# 5V_-5V_3_3V_PowerSupply.net
KiCad netlist of a schematic drawn in EAGLE
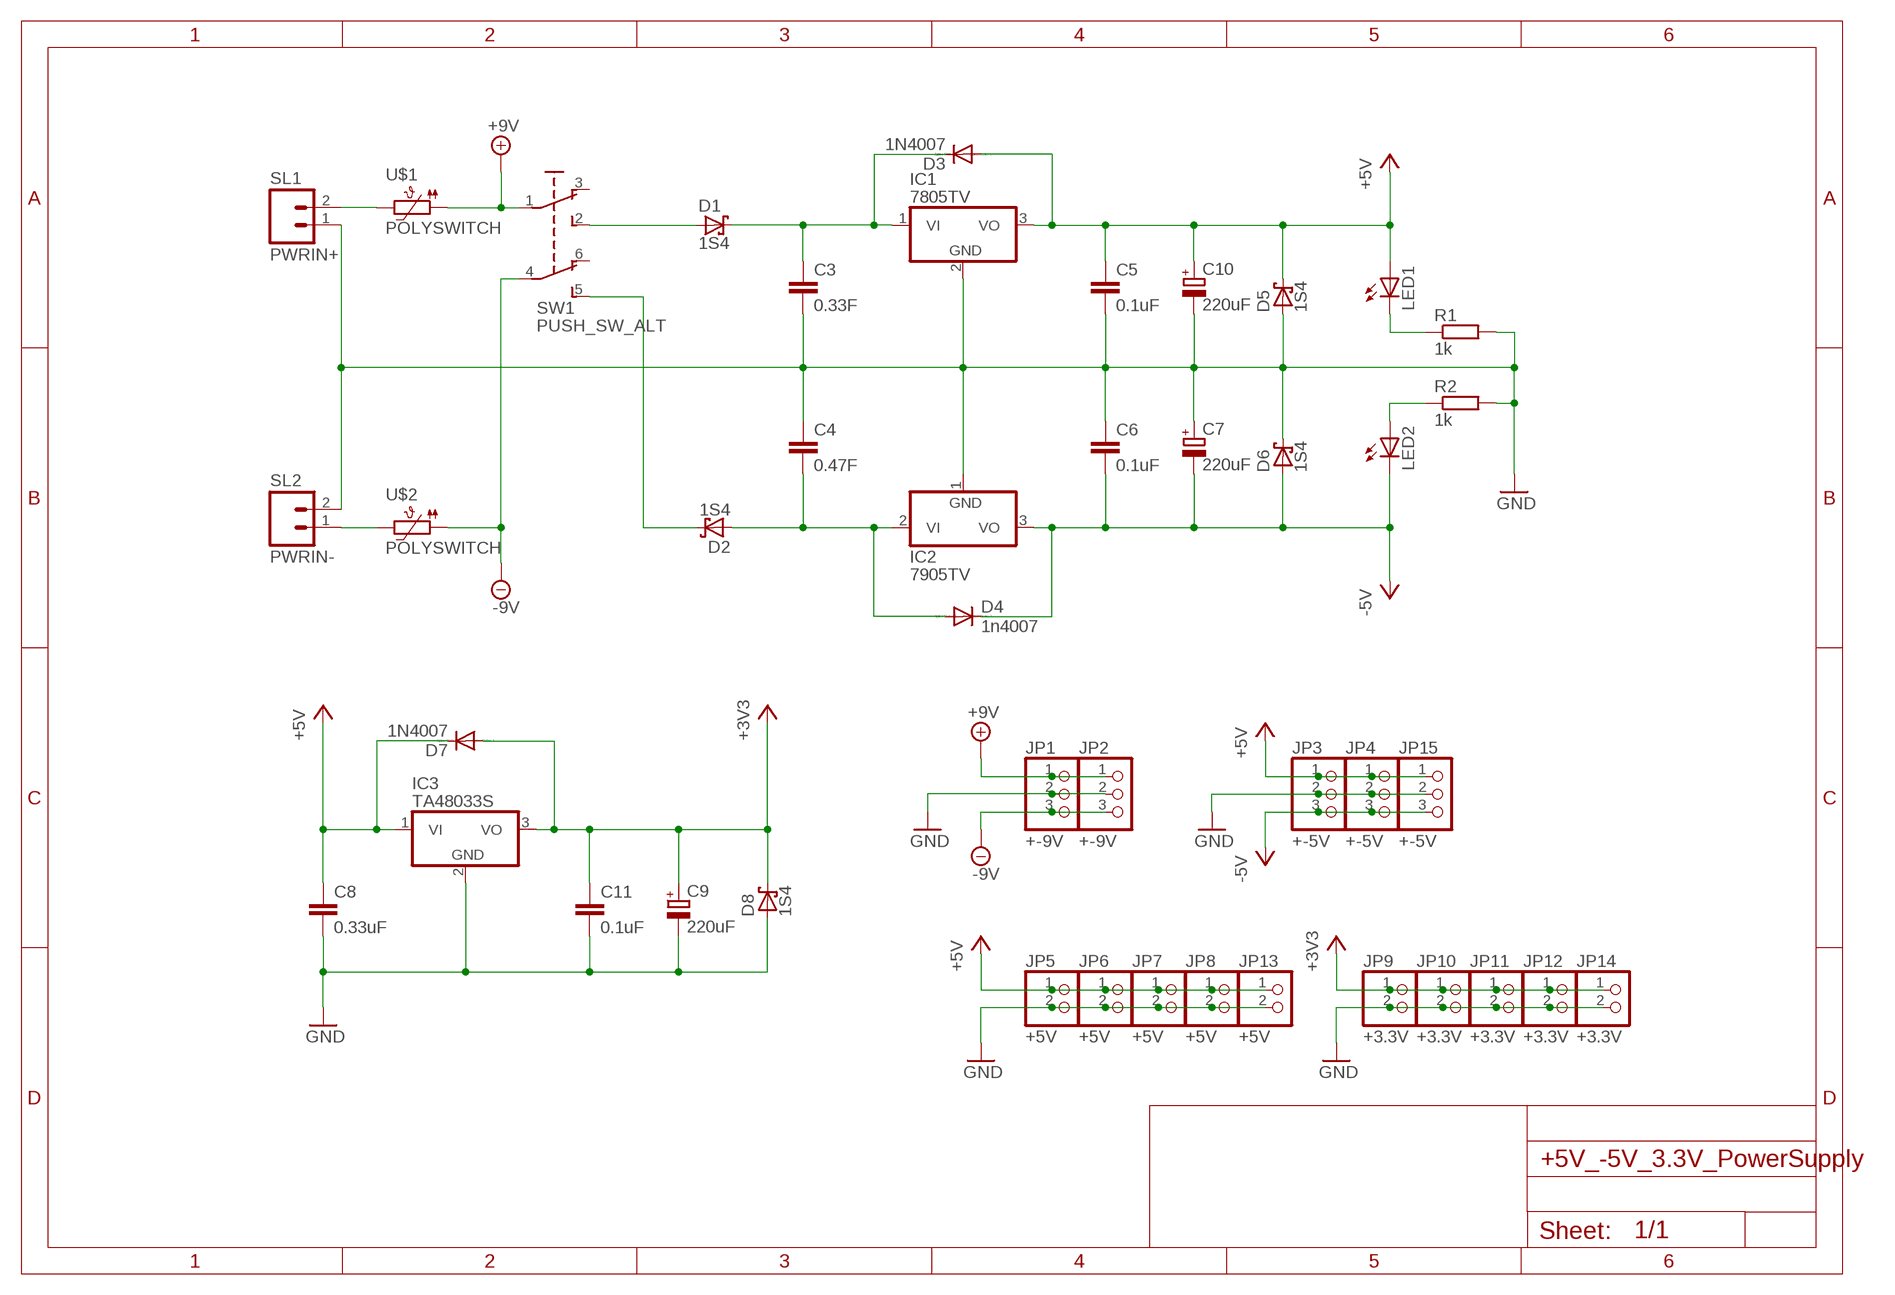
[diagram p0: schematic, sheet 1]

(export (version "E")
  (design (tool "Eeschema 10.0.6"))
  (components
    (comp (ref "C3")
      (value "0.33F")
      (footprint "eagle-import:C050-025X075")
      (libsource (lib "eagle-import") (part "C-EU050-025X075"))
    )
    (comp (ref "C4")
      (value "0.47F")
      (footprint "eagle-import:C050-025X075")
      (libsource (lib "eagle-import") (part "C-EU050-025X075"))
    )
    (comp (ref "C5")
      (value "0.1uF")
      (footprint "eagle-import:C050-024X044")
      (libsource (lib "eagle-import") (part "C-EU050-024X044"))
    )
    (comp (ref "C6")
      (value "0.1uF")
      (footprint "eagle-import:C050-024X044")
      (libsource (lib "eagle-import") (part "C-EU050-024X044"))
    )
    (comp (ref "C7")
      (value "220uF")
      (footprint "eagle-import:E2,5-6")
      (libsource (lib "eagle-import") (part "CPOL-EUE2.5-6"))
    )
    (comp (ref "C8")
      (value "0.33uF")
      (footprint "eagle-import:C050-025X075")
      (libsource (lib "eagle-import") (part "C-EU050-025X075"))
    )
    (comp (ref "C9")
      (value "220uF")
      (footprint "eagle-import:E2,5-6")
      (libsource (lib "eagle-import") (part "CPOL-EUE2.5-6"))
    )
    (comp (ref "C10")
      (value "220uF")
      (footprint "eagle-import:E2,5-6")
      (libsource (lib "eagle-import") (part "CPOL-EUE2.5-6"))
    )
    (comp (ref "C11")
      (value "0.1uF")
      (footprint "eagle-import:C050-025X075")
      (libsource (lib "eagle-import") (part "C-EU050-025X075"))
    )
    (comp (ref "D1")
      (value "1S4")
      (footprint "eagle-import:DO35-7")
      (libsource (lib "eagle-import") (part "SCHOTTKY-DIODEDO35-7"))
    )
    (comp (ref "D2")
      (value "1S4")
      (footprint "eagle-import:DO35-7")
      (libsource (lib "eagle-import") (part "SCHOTTKY-DIODEDO35-7"))
    )
    (comp (ref "D3")
      (value "1N4007")
      (footprint "eagle-import:D-7.5")
      (libsource (lib "eagle-import") (part "DIODE-D-7.5"))
    )
    (comp (ref "D4")
      (value "1n4007")
      (footprint "eagle-import:D-7.5")
      (libsource (lib "eagle-import") (part "DIODE-D-7.5"))
    )
    (comp (ref "D5")
      (value "1S4")
      (footprint "eagle-import:DO35-7")
      (libsource (lib "eagle-import") (part "SCHOTTKY-DIODEDO35-7"))
    )
    (comp (ref "D6")
      (value "1S4")
      (footprint "eagle-import:DO35-7")
      (libsource (lib "eagle-import") (part "SCHOTTKY-DIODEDO35-7"))
    )
    (comp (ref "D7")
      (value "1N4007")
      (footprint "eagle-import:D-7.5")
      (libsource (lib "eagle-import") (part "DIODE-D-7.5"))
    )
    (comp (ref "D8")
      (value "1S4")
      (footprint "eagle-import:DO35-7")
      (libsource (lib "eagle-import") (part "SCHOTTKY-DIODEDO35-7"))
    )
    (comp (ref "IC1")
      (value "7805TV")
      (footprint "eagle-import:TO220V")
      (libsource (lib "eagle-import") (part "78TV05"))
    )
    (comp (ref "IC2")
      (value "7905TV")
      (footprint "eagle-import:TO220V")
      (libsource (lib "eagle-import") (part "7905TV"))
    )
    (comp (ref "IC3")
      (value "TA48033S")
      (footprint "eagle-import:TO220V")
      (libsource (lib "eagle-import") (part "78TV05"))
    )
    (comp (ref "JP1")
      (value "+-9V")
      (footprint "eagle-import:1X03")
      (libsource (lib "eagle-import") (part "PINHD-1X3"))
    )
    (comp (ref "JP2")
      (value "+-9V")
      (footprint "eagle-import:1X03")
      (libsource (lib "eagle-import") (part "PINHD-1X3"))
    )
    (comp (ref "JP3")
      (value "+-5V")
      (footprint "eagle-import:1X03")
      (libsource (lib "eagle-import") (part "PINHD-1X3"))
    )
    (comp (ref "JP4")
      (value "+-5V")
      (footprint "eagle-import:1X03")
      (libsource (lib "eagle-import") (part "PINHD-1X3"))
    )
    (comp (ref "JP5")
      (value "+5V")
      (footprint "eagle-import:1X02")
      (libsource (lib "eagle-import") (part "PINHD-1X2"))
    )
    (comp (ref "JP6")
      (value "+5V")
      (footprint "eagle-import:1X02")
      (libsource (lib "eagle-import") (part "PINHD-1X2"))
    )
    (comp (ref "JP7")
      (value "+5V")
      (footprint "eagle-import:1X02")
      (libsource (lib "eagle-import") (part "PINHD-1X2"))
    )
    (comp (ref "JP8")
      (value "+5V")
      (footprint "eagle-import:1X02")
      (libsource (lib "eagle-import") (part "PINHD-1X2"))
    )
    (comp (ref "JP9")
      (value "+3.3V")
      (footprint "eagle-import:1X02")
      (libsource (lib "eagle-import") (part "PINHD-1X2"))
    )
    (comp (ref "JP10")
      (value "+3.3V")
      (footprint "eagle-import:1X02")
      (libsource (lib "eagle-import") (part "PINHD-1X2"))
    )
    (comp (ref "JP11")
      (value "+3.3V")
      (footprint "eagle-import:1X02")
      (libsource (lib "eagle-import") (part "PINHD-1X2"))
    )
    (comp (ref "JP12")
      (value "+3.3V")
      (footprint "eagle-import:1X02")
      (libsource (lib "eagle-import") (part "PINHD-1X2"))
    )
    (comp (ref "JP13")
      (value "+5V")
      (footprint "eagle-import:1X02")
      (libsource (lib "eagle-import") (part "PINHD-1X2"))
    )
    (comp (ref "JP14")
      (value "+3.3V")
      (footprint "eagle-import:1X02")
      (libsource (lib "eagle-import") (part "PINHD-1X2"))
    )
    (comp (ref "JP15")
      (value "+-5V")
      (footprint "eagle-import:1X03")
      (libsource (lib "eagle-import") (part "PINHD-1X3"))
    )
    (comp (ref "LED1")
      (value "LED3MM")
      (footprint "eagle-import:LED3MM")
      (libsource (lib "eagle-import") (part "LED3MM"))
    )
    (comp (ref "LED2")
      (value "LED3MM")
      (footprint "eagle-import:LED3MM")
      (libsource (lib "eagle-import") (part "LED3MM"))
    )
    (comp (ref "R1")
      (value "1k")
      (footprint "eagle-import:0207_7")
      (libsource (lib "eagle-import") (part "R-EU_0207/7"))
    )
    (comp (ref "R2")
      (value "1k")
      (footprint "eagle-import:0207_7")
      (libsource (lib "eagle-import") (part "R-EU_0207/7"))
    )
    (comp (ref "SL1")
      (value "PWRIN+")
      (footprint "eagle-import:02P")
      (libsource (lib "eagle-import") (part "M02"))
    )
    (comp (ref "SL2")
      (value "PWRIN-")
      (footprint "eagle-import:02P")
      (libsource (lib "eagle-import") (part "M02"))
    )
    (comp (ref "SW1")
      (value "PUSH_SW_ALT")
      (footprint "eagle-import:PUSH_SW_ALT")
      (libsource (lib "eagle-import") (part "PUSH_SW_ALT"))
    )
    (comp (ref "U$1")
      (value "POLYSWITCH")
      (footprint "eagle-import:POLYSWITCH")
      (libsource (lib "eagle-import") (part "POLYSWITCH"))
    )
    (comp (ref "U$2")
      (value "POLYSWITCH")
      (footprint "eagle-import:POLYSWITCH")
      (libsource (lib "eagle-import") (part "POLYSWITCH"))
    )
  )
  (nets
    (net (code "1") (name "+3V3") (class "Default")
      (node (ref "C11") (pin "1") (pinfunction "1_1") (pintype "passive"))
      (node (ref "C9") (pin "+") (pinfunction "+_+") (pintype "passive"))
      (node (ref "D7") (pin "A") (pinfunction "A_A") (pintype "passive"))
      (node (ref "D8") (pin "C") (pinfunction "C_C") (pintype "passive"))
      (node (ref "IC3") (pin "3") (pinfunction "VO_3") (pintype "passive"))
      (node (ref "JP10") (pin "1") (pinfunction "1_1") (pintype "passive"))
      (node (ref "JP11") (pin "1") (pinfunction "1_1") (pintype "passive"))
      (node (ref "JP12") (pin "1") (pinfunction "1_1") (pintype "passive"))
      (node (ref "JP14") (pin "1") (pinfunction "1_1") (pintype "passive"))
      (node (ref "JP9") (pin "1") (pinfunction "1_1") (pintype "passive"))
    )
    (net (code "2") (name "+5V") (class "Default")
      (node (ref "C10") (pin "+") (pinfunction "+_+") (pintype "passive"))
      (node (ref "C5") (pin "1") (pinfunction "1_1") (pintype "passive"))
      (node (ref "C8") (pin "1") (pinfunction "1_1") (pintype "passive"))
      (node (ref "D3") (pin "A") (pinfunction "A_A") (pintype "passive"))
      (node (ref "D5") (pin "C") (pinfunction "C_C") (pintype "passive"))
      (node (ref "D7") (pin "C") (pinfunction "C_C") (pintype "passive"))
      (node (ref "IC1") (pin "3") (pinfunction "VO_3") (pintype "passive"))
      (node (ref "IC3") (pin "1") (pinfunction "VI_1") (pintype "input"))
      (node (ref "JP13") (pin "1") (pinfunction "1_1") (pintype "passive"))
      (node (ref "JP15") (pin "1") (pinfunction "1_1") (pintype "passive"))
      (node (ref "JP3") (pin "1") (pinfunction "1_1") (pintype "passive"))
      (node (ref "JP4") (pin "1") (pinfunction "1_1") (pintype "passive"))
      (node (ref "JP5") (pin "1") (pinfunction "1_1") (pintype "passive"))
      (node (ref "JP6") (pin "1") (pinfunction "1_1") (pintype "passive"))
      (node (ref "JP7") (pin "1") (pinfunction "1_1") (pintype "passive"))
      (node (ref "JP8") (pin "1") (pinfunction "1_1") (pintype "passive"))
      (node (ref "LED1") (pin "A") (pinfunction "A_A") (pintype "passive"))
    )
    (net (code "3") (name "+9V") (class "Default")
      (node (ref "JP1") (pin "1") (pinfunction "1_1") (pintype "passive"))
      (node (ref "JP2") (pin "1") (pinfunction "1_1") (pintype "passive"))
      (node (ref "SW1") (pin "1") (pinfunction "P_1") (pintype "passive"))
      (node (ref "U$1") (pin "1") (pinfunction "1_1") (pintype "passive"))
    )
    (net (code "4") (name "-5V") (class "Default")
      (node (ref "C6") (pin "2") (pinfunction "2_2") (pintype "passive"))
      (node (ref "C7") (pin "-") (pinfunction "-_-") (pintype "passive"))
      (node (ref "D4") (pin "C") (pinfunction "C_C") (pintype "passive"))
      (node (ref "D6") (pin "A") (pinfunction "A_A") (pintype "passive"))
      (node (ref "IC2") (pin "3") (pinfunction "VO_3") (pintype "passive"))
      (node (ref "JP15") (pin "3") (pinfunction "3_3") (pintype "passive"))
      (node (ref "JP3") (pin "3") (pinfunction "3_3") (pintype "passive"))
      (node (ref "JP4") (pin "3") (pinfunction "3_3") (pintype "passive"))
      (node (ref "LED2") (pin "K") (pinfunction "C_K") (pintype "passive"))
    )
    (net (code "5") (name "-9V") (class "Default")
      (node (ref "JP1") (pin "3") (pinfunction "3_3") (pintype "passive"))
      (node (ref "JP2") (pin "3") (pinfunction "3_3") (pintype "passive"))
      (node (ref "SW1") (pin "4") (pinfunction "P1_4") (pintype "passive"))
      (node (ref "U$2") (pin "1") (pinfunction "1_1") (pintype "passive"))
    )
    (net (code "6") (name "GND") (class "Default")
      (node (ref "C10") (pin "-") (pinfunction "-_-") (pintype "passive"))
      (node (ref "C11") (pin "2") (pinfunction "2_2") (pintype "passive"))
      (node (ref "C3") (pin "2") (pinfunction "2_2") (pintype "passive"))
      (node (ref "C4") (pin "1") (pinfunction "1_1") (pintype "passive"))
      (node (ref "C5") (pin "2") (pinfunction "2_2") (pintype "passive"))
      (node (ref "C6") (pin "1") (pinfunction "1_1") (pintype "passive"))
      (node (ref "C7") (pin "+") (pinfunction "+_+") (pintype "passive"))
      (node (ref "C8") (pin "2") (pinfunction "2_2") (pintype "passive"))
      (node (ref "C9") (pin "-") (pinfunction "-_-") (pintype "passive"))
      (node (ref "D5") (pin "A") (pinfunction "A_A") (pintype "passive"))
      (node (ref "D6") (pin "C") (pinfunction "C_C") (pintype "passive"))
      (node (ref "D8") (pin "A") (pinfunction "A_A") (pintype "passive"))
      (node (ref "IC1") (pin "2") (pinfunction "GND_2") (pintype "passive"))
      (node (ref "IC2") (pin "1") (pinfunction "GND_1") (pintype "passive"))
      (node (ref "IC3") (pin "2") (pinfunction "GND_2") (pintype "passive"))
      (node (ref "JP1") (pin "2") (pinfunction "2_2") (pintype "passive"))
      (node (ref "JP10") (pin "2") (pinfunction "2_2") (pintype "passive"))
      (node (ref "JP11") (pin "2") (pinfunction "2_2") (pintype "passive"))
      (node (ref "JP12") (pin "2") (pinfunction "2_2") (pintype "passive"))
      (node (ref "JP13") (pin "2") (pinfunction "2_2") (pintype "passive"))
      (node (ref "JP14") (pin "2") (pinfunction "2_2") (pintype "passive"))
      (node (ref "JP15") (pin "2") (pinfunction "2_2") (pintype "passive"))
      (node (ref "JP2") (pin "2") (pinfunction "2_2") (pintype "passive"))
      (node (ref "JP3") (pin "2") (pinfunction "2_2") (pintype "passive"))
      (node (ref "JP4") (pin "2") (pinfunction "2_2") (pintype "passive"))
      (node (ref "JP5") (pin "2") (pinfunction "2_2") (pintype "passive"))
      (node (ref "JP6") (pin "2") (pinfunction "2_2") (pintype "passive"))
      (node (ref "JP7") (pin "2") (pinfunction "2_2") (pintype "passive"))
      (node (ref "JP8") (pin "2") (pinfunction "2_2") (pintype "passive"))
      (node (ref "JP9") (pin "2") (pinfunction "2_2") (pintype "passive"))
      (node (ref "R1") (pin "2") (pinfunction "2_2") (pintype "passive"))
      (node (ref "R2") (pin "2") (pinfunction "2_2") (pintype "passive"))
      (node (ref "SL1") (pin "1") (pinfunction "1_1") (pintype "passive"))
      (node (ref "SL2") (pin "2") (pinfunction "2_2") (pintype "passive"))
    )
    (net (code "7") (name "Net-(IC1-VI)") (class "Default")
      (node (ref "C3") (pin "1") (pinfunction "1_1") (pintype "passive"))
      (node (ref "D1") (pin "C") (pinfunction "C_C") (pintype "passive"))
      (node (ref "D3") (pin "C") (pinfunction "C_C") (pintype "passive"))
      (node (ref "IC1") (pin "1") (pinfunction "VI_1") (pintype "input"))
    )
    (net (code "8") (name "Net-(IC2-VI)") (class "Default")
      (node (ref "C4") (pin "2") (pinfunction "2_2") (pintype "passive"))
      (node (ref "D2") (pin "A") (pinfunction "A_A") (pintype "passive"))
      (node (ref "D4") (pin "A") (pinfunction "A_A") (pintype "passive"))
      (node (ref "IC2") (pin "2") (pinfunction "VI_2") (pintype "input"))
    )
    (net (code "9") (name "Net-(LED1-C)") (class "Default")
      (node (ref "LED1") (pin "K") (pinfunction "C_K") (pintype "passive"))
      (node (ref "R1") (pin "1") (pinfunction "1_1") (pintype "passive"))
    )
    (net (code "10") (name "Net-(LED2-PadA)") (class "Default")
      (node (ref "LED2") (pin "A") (pinfunction "A_A") (pintype "passive"))
      (node (ref "R2") (pin "1") (pinfunction "1_1") (pintype "passive"))
    )
    (net (code "11") (name "Net-(SL1-Pad2)") (class "Default")
      (node (ref "SL1") (pin "2") (pinfunction "2_2") (pintype "passive"))
      (node (ref "U$1") (pin "2") (pinfunction "2_2") (pintype "passive"))
    )
    (net (code "12") (name "Net-(SL2-Pad1)") (class "Default")
      (node (ref "SL2") (pin "1") (pinfunction "1_1") (pintype "passive"))
      (node (ref "U$2") (pin "2") (pinfunction "2_2") (pintype "passive"))
    )
    (net (code "13") (name "Net-(SW1-S)") (class "Default")
      (node (ref "D1") (pin "A") (pinfunction "A_A") (pintype "passive"))
      (node (ref "SW1") (pin "2") (pinfunction "S_2") (pintype "passive"))
    )
    (net (code "14") (name "Net-(SW1-S1)") (class "Default")
      (node (ref "D2") (pin "C") (pinfunction "C_C") (pintype "passive"))
      (node (ref "SW1") (pin "5") (pinfunction "S1_5") (pintype "passive"))
    )
    (net (code "15") (name "unconnected-(SW1-O-Pad3)") (class "Default")
      (node (ref "SW1") (pin "3") (pinfunction "O_3") (pintype "passive"))
    )
    (net (code "16") (name "unconnected-(SW1-O1-Pad6)") (class "Default")
      (node (ref "SW1") (pin "6") (pinfunction "O1_6") (pintype "passive"))
    )
  )
)
